# 1_Power.net
KiCad netlist of a schematic drawn in Altium Designer
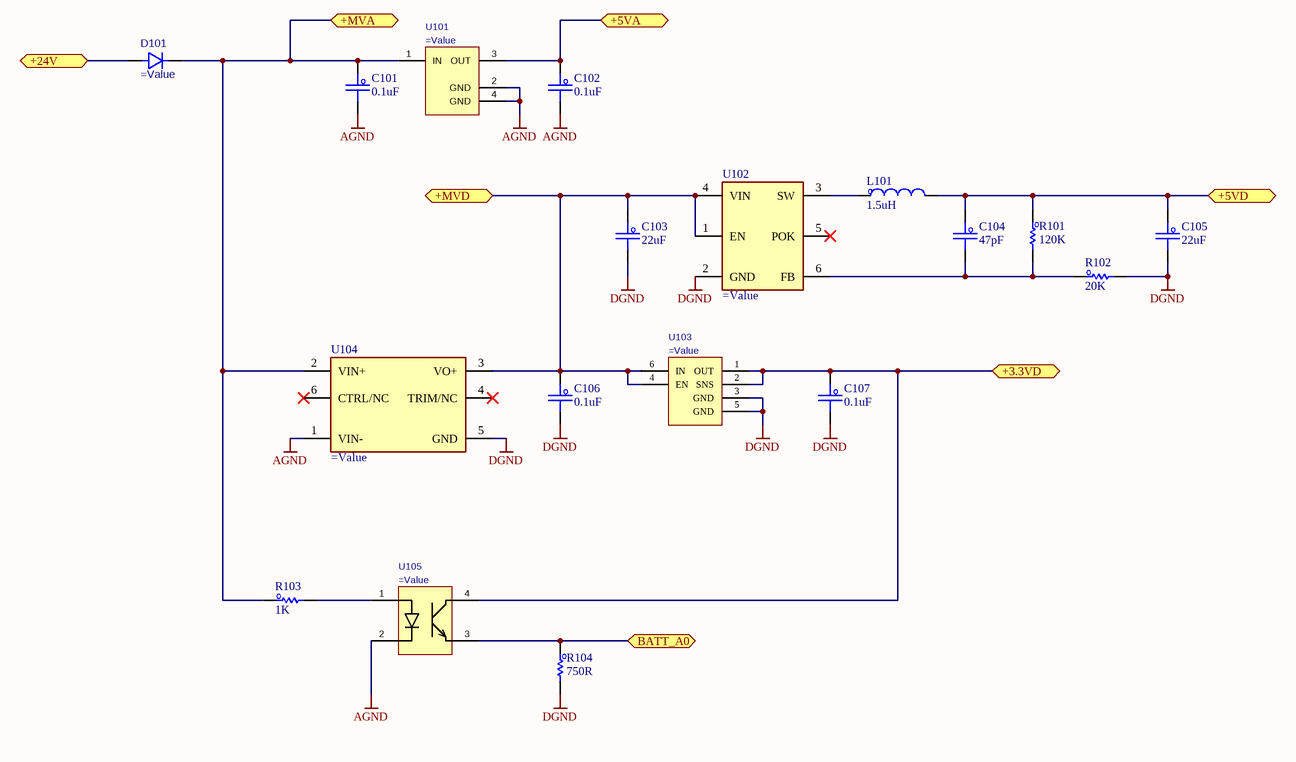
[diagram p0: 1_Power.SchDoc]

(export (version "E")
  (design (tool "Eeschema 10.0.6"))
  (components
    (comp (ref "C101")
      (value "0.1uF")
      (footprint "C_0603")
      (description "CAP CER 0.1UF 50V X7R 0603")
      (fields (field (name "MANUFACTURER") "KEMET") (field (name "PARTNUMBER") "C0603C104K5RACTU"))
      (libsource (lib "UUSymbol") (part "C_Capacitor"))
    )
    (comp (ref "C102")
      (value "0.1uF")
      (footprint "C_0603")
      (description "CAP CER 0.1UF 50V X7R 0603")
      (fields (field (name "MANUFACTURER") "KEMET") (field (name "PARTNUMBER") "C0603C104K5RACTU"))
      (libsource (lib "UUSymbol") (part "C_Capacitor"))
    )
    (comp (ref "C103")
      (value "22uF")
      (footprint "C_0603")
      (description "CAP CER 22UF 10V X5R 0603")
      (fields
        (field (name "MANUFACTURER") "TDK Corporation")
        (field (name "PARTNUMBER") "C1608X5R1A226M080AC")
      )
      (libsource (lib "UUSymbol") (part "C_Capacitor"))
    )
    (comp (ref "C104")
      (value "47pF")
      (footprint "C_0603")
      (description "CAP CER 47PF 50V X7R 0603")
      (fields (field (name "MANUFACTURER") "KEMET") (field (name "PARTNUMBER") "C0603C470J5RAC7867"))
      (libsource (lib "UUSymbol") (part "C_Capacitor"))
    )
    (comp (ref "C105")
      (value "22uF")
      (footprint "C_0603")
      (description "CAP CER 22UF 10V X5R 0603")
      (fields
        (field (name "MANUFACTURER") "TDK Corporation")
        (field (name "PARTNUMBER") "C1608X5R1A226M080AC")
      )
      (libsource (lib "UUSymbol") (part "C_Capacitor"))
    )
    (comp (ref "C106")
      (value "0.1uF")
      (footprint "C_0603")
      (description "CAP CER 0.1UF 50V X7R 0603")
      (fields (field (name "MANUFACTURER") "KEMET") (field (name "PARTNUMBER") "C0603C104K5RACTU"))
      (libsource (lib "UUSymbol") (part "C_Capacitor"))
    )
    (comp (ref "C107")
      (value "0.1uF")
      (footprint "C_0603")
      (description "CAP CER 0.1UF 50V X7R 0603")
      (fields (field (name "MANUFACTURER") "KEMET") (field (name "PARTNUMBER") "C0603C104K5RACTU"))
      (libsource (lib "UUSymbol") (part "C_Capacitor"))
    )
    (comp (ref "D101")
      (value "~")
      (footprint "SOD323")
      (description "DIODE SCHOTTKY 40V 2A 0603")
      (fields (field (name "MANUFACTURER") "Slkor(SLKORMICRO Elec.)") (field (name "PARTNUMBER") "SD103AWS"))
      (libsource (lib "UUSymbol") (part "D_PW_SD103AWS"))
    )
    (comp (ref "L101")
      (value "1.5uH")
      (footprint "L_0603")
      (description "1.5 µH Shielded Wirewound Inductor 1 A 200mOhm Max 0603 (1608 Metric)")
      (fields (field (name "MANUFACTURER") "Taiyo Yuden") (field (name "PARTNUMBER") "MBKK1608T1R5M"))
      (libsource (lib "UUSymbol") (part "L_Inductor"))
    )
    (comp (ref "R101")
      (value "120K")
      (footprint "R_0603")
      (description "RES 120K OHM 5% 1/10W 0603")
      (fields (field (name "MANUFACTURER") "YAGEO") (field (name "PARTNUMBER") "RC0603JR-07120KL"))
      (libsource (lib "UUSymbol") (part "R_Resister"))
    )
    (comp (ref "R102")
      (value "20K")
      (footprint "R_0603")
      (description "RES 20K OHM 1% 1/10W 0603")
      (fields (field (name "MANUFACTURER") "YAGEO") (field (name "PARTNUMBER") "RC0603FR-0720KL"))
      (libsource (lib "UUSymbol") (part "R_Resister"))
    )
    (comp (ref "R103")
      (value "1K")
      (footprint "R_0603")
      (description "RES SMD 1K OHM 5% 1/10W 0603")
      (fields (field (name "MANUFACTURER") "Vishay Dale") (field (name "PARTNUMBER") "CRCW06031K00JNEA"))
      (libsource (lib "UUSymbol") (part "R_Resister"))
    )
    (comp (ref "R104")
      (value "750R")
      (footprint "R_0603")
      (description "RES 715 OHM 0.1% 0.15W 0603")
      (fields (field (name "MANUFACTURER") "Vishay Dale") (field (name "PARTNUMBER") "RCS0603750RFKEA"))
      (libsource (lib "UUSymbol") (part "R_Resister"))
    )
    (comp (ref "U101")
      (value "~")
      (footprint "SOT230P700X180-4N")
      (description "IC REG LINEAR 5V 500MA SOT223-4")
      (fields
        (field (name "PARTNUMBER") "UA78M05QDCYRG4Q1")
        (field (name "MANUFACTURER") "Texas Instruments")
      )
      (libsource (lib "UUSymbol") (part "IC_LDO_UA78M05QDCYRG4Q1"))
    )
    (comp (ref "U102")
      (value "~")
      (footprint "SOT95P270X115-6M")
      (description "DC DC CONVERTER 5V 5W")
      (fields (field (name "PARTNUMBER") "JW5222") (field (name "MANUFACTURER") "JoulWatt Tech"))
      (libsource (lib "UUSymbol") (part "IC_PMS_JW5222"))
    )
    (comp (ref "U103")
      (value "~")
      (footprint "SON65P200X200X80-7N")
      (description "IC REG LINEAR 3.3V 1A 6WSON")
      (fields (field (name "PARTNUMBER") "TLV76733DRVR") (field (name "MANUFACTURER") "Texas Instruments"))
      (libsource (lib "UUSymbol") (part "IC_LDO_TLV76733DRVR"))
    )
    (comp (ref "U104")
      (value "~")
      (footprint "CONV_HLK-20D2405")
      (description "20W DC/DC IN 9-36V OUT 5V")
      (fields (field (name "MANUFACTURER") "HI-LINK") (field (name "PARTNUMBER") "HLK-10D2405"))
      (libsource (lib "UUSymbol") (part "IC_PMS_HLK-X0D2405"))
    )
    (comp (ref "U105")
      (value "~")
      (footprint "SOIC_M618A-3T_VI")
      (description "OPTOISOLATOR 3.75KV TRANS 4-SOP")
      (fields (field (name "MANUFACTURER") "Vishay") (field (name "PARTNUMBER") "VOM618A-3T"))
      (libsource (lib "UUSymbol") (part "IC_OPTO_VOM618A-3T"))
    )
  )
  (nets
    (net (code "1") (name "/+3.3VD") (class "Default")
      (node (ref "C107") (pin "1") (pinfunction "1_1") (pintype "passive"))
      (node (ref "U103") (pin "1") (pinfunction "OUT_1") (pintype "passive"))
      (node (ref "U103") (pin "2") (pinfunction "SNS_2") (pintype "passive"))
      (node (ref "U105") (pin "4") (pinfunction "C_4") (pintype "passive"))
    )
    (net (code "2") (name "/+5VA") (class "Default")
      (node (ref "C102") (pin "1") (pinfunction "1_1") (pintype "passive"))
      (node (ref "U101") (pin "3") (pinfunction "OUT_3") (pintype "passive"))
    )
    (net (code "3") (name "/+5VD") (class "Default")
      (node (ref "C104") (pin "1") (pinfunction "1_1") (pintype "passive"))
      (node (ref "C105") (pin "1") (pinfunction "1_1") (pintype "passive"))
      (node (ref "L101") (pin "2") (pinfunction "2_2") (pintype "passive"))
      (node (ref "R101") (pin "1") (pinfunction "1_1") (pintype "passive"))
    )
    (net (code "4") (name "/+24V") (class "Default")
      (node (ref "D101") (pin "2") (pinfunction "2_2") (pintype "passive"))
    )
    (net (code "5") (name "/+MVA") (class "Default")
      (node (ref "C101") (pin "1") (pinfunction "1_1") (pintype "passive"))
      (node (ref "D101") (pin "1") (pinfunction "1_1") (pintype "passive"))
      (node (ref "R103") (pin "1") (pinfunction "1_1") (pintype "passive"))
      (node (ref "U101") (pin "1") (pinfunction "IN_1") (pintype "passive"))
      (node (ref "U104") (pin "2") (pinfunction "VIN+_2") (pintype "passive"))
    )
    (net (code "6") (name "/+MVD") (class "Default")
      (node (ref "C103") (pin "1") (pinfunction "1_1") (pintype "passive"))
      (node (ref "C106") (pin "1") (pinfunction "1_1") (pintype "passive"))
      (node (ref "U102") (pin "1") (pinfunction "EN_1") (pintype "passive"))
      (node (ref "U102") (pin "4") (pinfunction "VIN_4") (pintype "passive"))
      (node (ref "U103") (pin "4") (pinfunction "EN_4") (pintype "passive"))
      (node (ref "U103") (pin "6") (pinfunction "IN_6") (pintype "passive"))
      (node (ref "U104") (pin "3") (pinfunction "VO+_3") (pintype "passive"))
    )
    (net (code "7") (name "/BATT_A0") (class "Default")
      (node (ref "R104") (pin "1") (pinfunction "1_1") (pintype "passive"))
      (node (ref "U105") (pin "3") (pinfunction "E_3") (pintype "passive"))
    )
    (net (code "8") (name "AGND") (class "Default")
      (node (ref "C101") (pin "2") (pinfunction "2_2") (pintype "passive"))
      (node (ref "C102") (pin "2") (pinfunction "2_2") (pintype "passive"))
      (node (ref "U101") (pin "2") (pinfunction "GND_2") (pintype "passive"))
      (node (ref "U101") (pin "4") (pinfunction "GND_4") (pintype "passive"))
      (node (ref "U104") (pin "1") (pinfunction "VIN-_1") (pintype "passive"))
      (node (ref "U105") (pin "2") (pinfunction "C_2_2") (pintype "passive"))
    )
    (net (code "9") (name "DGND") (class "Default")
      (node (ref "C103") (pin "2") (pinfunction "2_2") (pintype "passive"))
      (node (ref "C105") (pin "2") (pinfunction "2_2") (pintype "passive"))
      (node (ref "C106") (pin "2") (pinfunction "2_2") (pintype "passive"))
      (node (ref "C107") (pin "2") (pinfunction "2_2") (pintype "passive"))
      (node (ref "R102") (pin "2") (pinfunction "2_2") (pintype "passive"))
      (node (ref "R104") (pin "2") (pinfunction "2_2") (pintype "passive"))
      (node (ref "U102") (pin "2") (pinfunction "GND_2") (pintype "passive"))
      (node (ref "U103") (pin "3") (pinfunction "GND_3") (pintype "passive"))
      (node (ref "U103") (pin "5") (pinfunction "GND_5") (pintype "passive"))
      (node (ref "U104") (pin "5") (pinfunction "GND_5") (pintype "passive"))
    )
    (net (code "10") (name "Net-(U102-FB)") (class "Default")
      (node (ref "C104") (pin "2") (pinfunction "2_2") (pintype "passive"))
      (node (ref "R101") (pin "2") (pinfunction "2_2") (pintype "passive"))
      (node (ref "R102") (pin "1") (pinfunction "1_1") (pintype "passive"))
      (node (ref "U102") (pin "6") (pinfunction "FB_6") (pintype "passive"))
    )
    (net (code "11") (name "Net-(U102-SW)") (class "Default")
      (node (ref "L101") (pin "1") (pinfunction "1_1") (pintype "passive"))
      (node (ref "U102") (pin "3") (pinfunction "SW_3") (pintype "passive"))
    )
    (net (code "12") (name "Net-(U105-A)") (class "Default")
      (node (ref "R103") (pin "2") (pinfunction "2_2") (pintype "passive"))
      (node (ref "U105") (pin "1") (pinfunction "A_1") (pintype "passive"))
    )
    (net (code "13") (name "unconnected-(U102-POK-Pad5)") (class "Default")
      (node (ref "U102") (pin "5") (pinfunction "POK_5") (pintype "passive+no_connect"))
    )
    (net (code "14") (name "unconnected-(U104-CTRL{slash}NC-Pad6)") (class "Default")
      (node (ref "U104") (pin "6") (pinfunction "CTRL/NC_6") (pintype "passive+no_connect"))
    )
    (net (code "15") (name "unconnected-(U104-TRIM{slash}NC-Pad4)") (class "Default")
      (node (ref "U104") (pin "4") (pinfunction "TRIM/NC_4") (pintype "passive+no_connect"))
    )
  )
)
